# PowerStage.net
KiCad netlist of a schematic drawn in Altium Designer
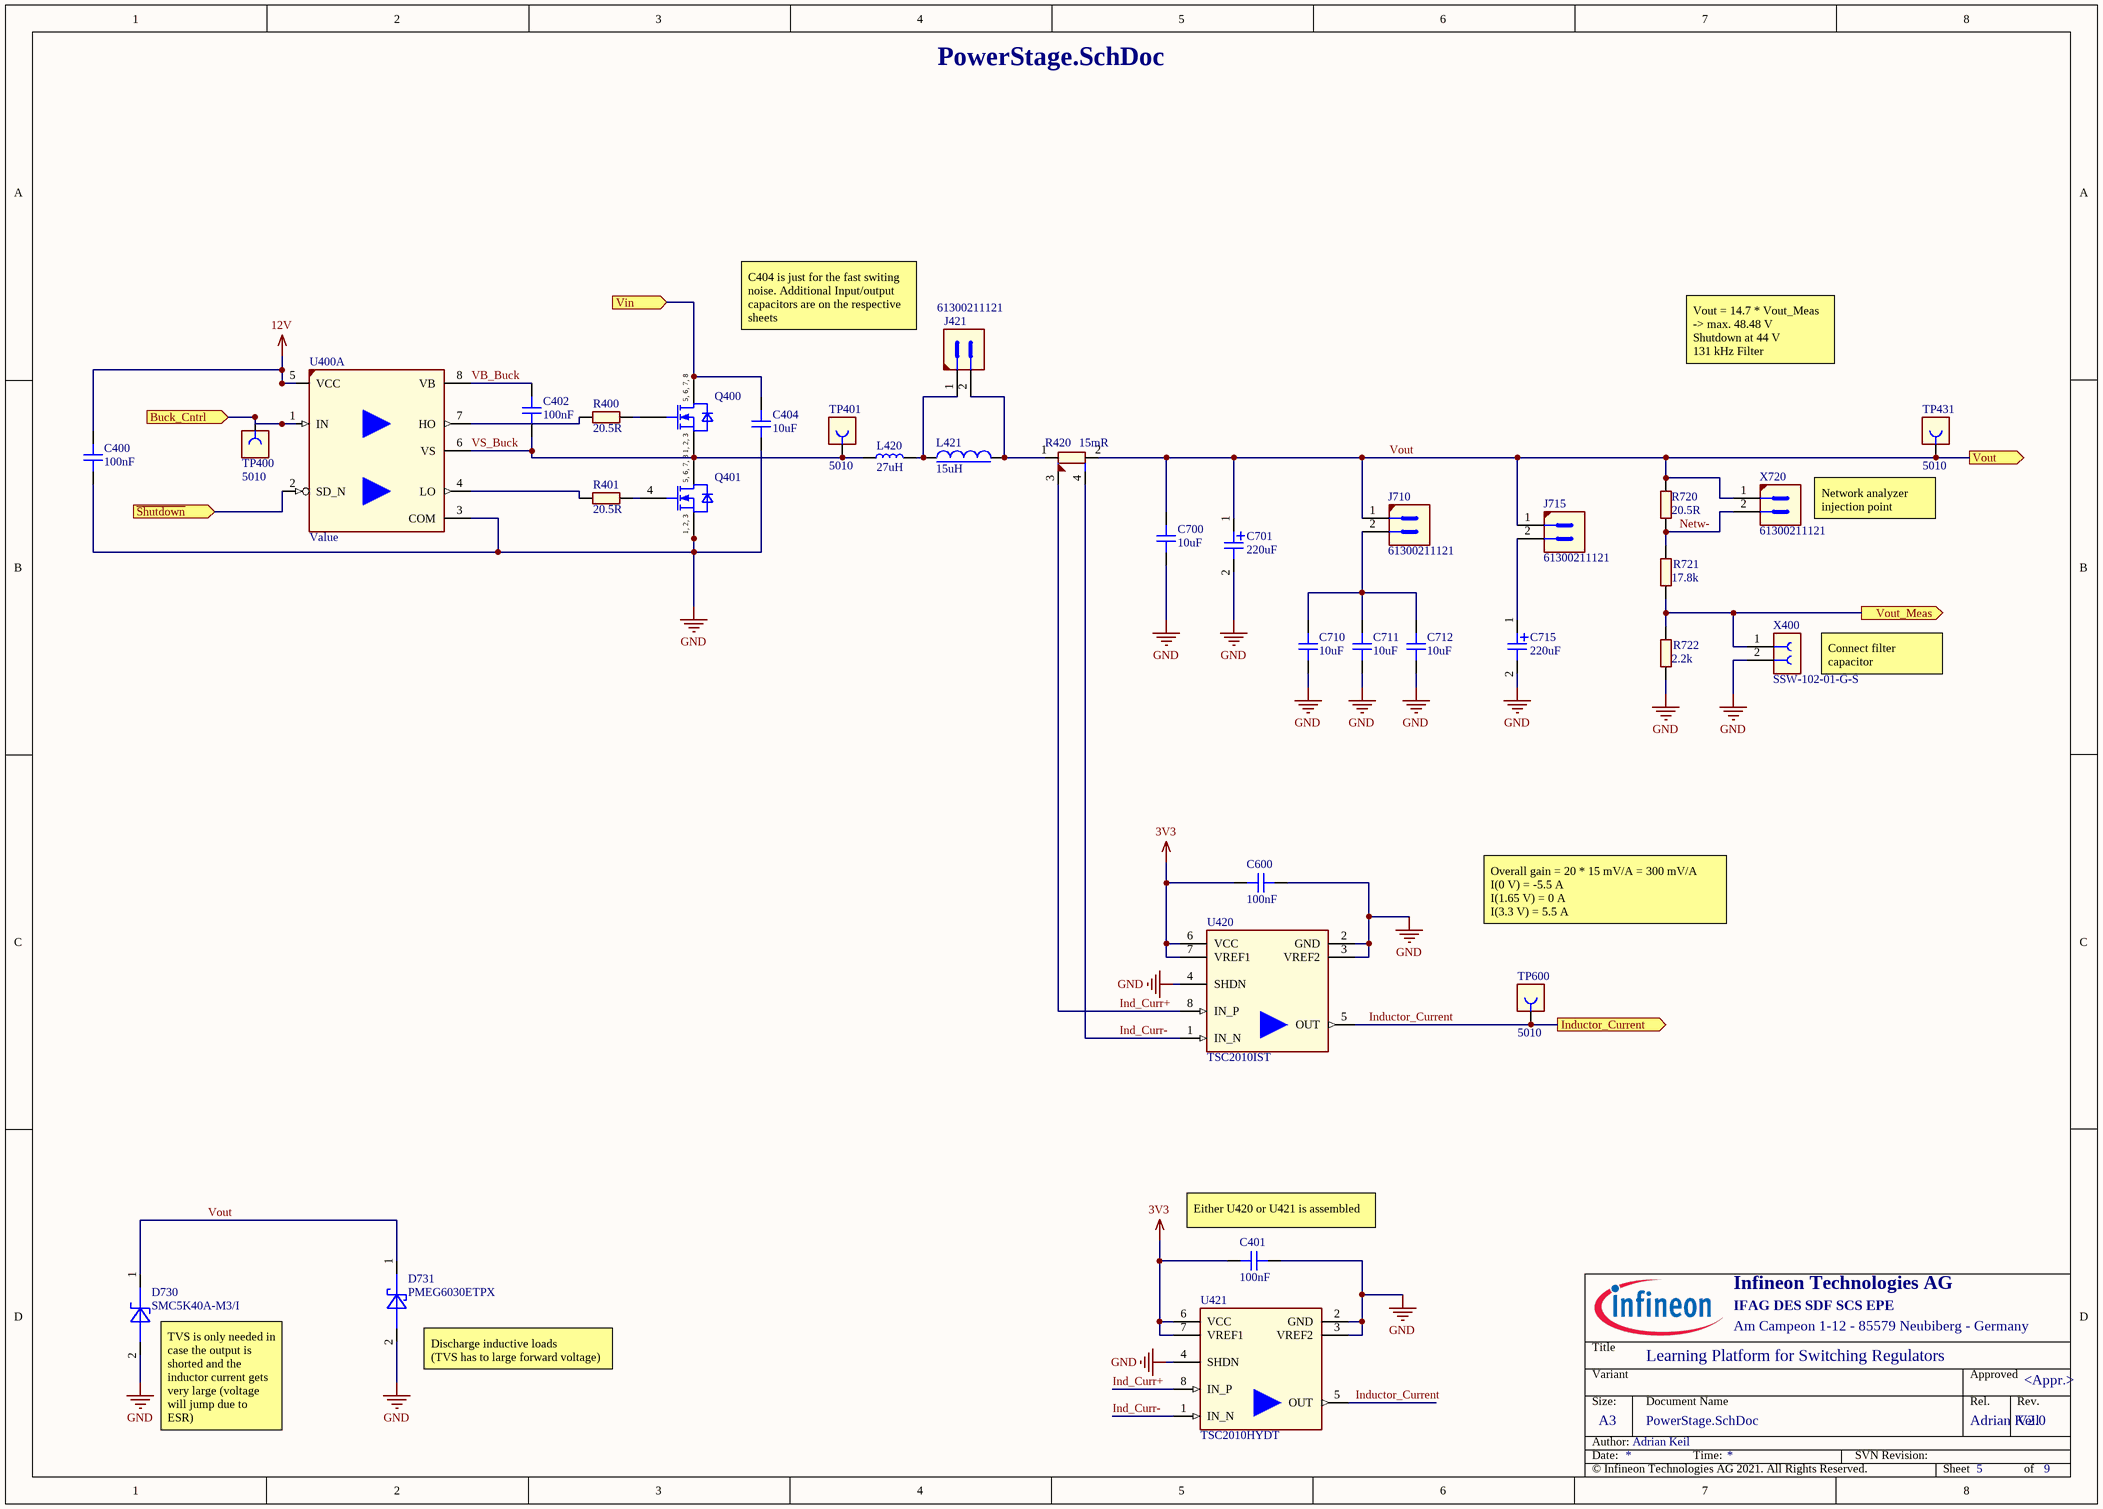
[diagram p0: PowerStage.SchDoc]

(export (version "E")
  (design (tool "Eeschema 10.0.6"))
  (components
    (comp (ref "C400")
      (value "100nF")
      (footprint "CAPC3216X125N-0")
      (description "CAP / CERA / 100nF / 50V / 10% / X7R (EIA) / -55°C to 125°C / 1206(3216) / SMD / -")
      (fields (field (name "LEGACY PARTNUMBER") "CAP01005660") (field (name "MANUFACTURER") "MuRata"))
      (libsource (lib "PCBLibraryData") (part "CAP-SGL-STD-02P_00000001"))
    )
    (comp (ref "C401")
      (value "100nF")
      (footprint "CAPC3216X125N-0")
      (description "CAP / CERA / 100nF / 50V / 10% / X7R (EIA) / -55°C to 125°C / 1206(3216) / SMD / -")
      (fields (field (name "LEGACY PARTNUMBER") "CAP01005660") (field (name "MANUFACTURER") "MuRata"))
      (libsource (lib "PCBLibraryData") (part "CAP-SGL-STD-02P_00000001"))
    )
    (comp (ref "C402")
      (value "100nF")
      (footprint "CAPC3216X125N-0")
      (description "CAP / CERA / 100nF / 50V / 10% / X7R (EIA) / -55°C to 125°C / 1206(3216) / SMD / -")
      (fields (field (name "LEGACY PARTNUMBER") "CAP01005660") (field (name "MANUFACTURER") "MuRata"))
      (libsource (lib "PCBLibraryData") (part "CAP-SGL-STD-02P_00000001"))
    )
    (comp (ref "C404")
      (value "10uF")
      (footprint "CAPC3216X190N-1")
      (description "CAP / CERA / 10uF / 50V / 20% / X5R (EIA) / -55°C to 85°C / 1206 (3216) / SMD / -")
      (fields (field (name "MANUFACTURER") "Taiyo Yuden"))
      (libsource (lib "PCBLibraryData") (part "CAP-SGL-STD-02P_00000001"))
    )
    (comp (ref "C600")
      (value "100nF")
      (footprint "CAPC3216X125N-0")
      (description "CAP / CERA / 100nF / 50V / 10% / X7R (EIA) / -55°C to 125°C / 1206(3216) / SMD / -")
      (fields (field (name "LEGACY PARTNUMBER") "CAP01005660") (field (name "MANUFACTURER") "MuRata"))
      (libsource (lib "PCBLibraryData") (part "CAP-SGL-STD-02P_00000001"))
    )
    (comp (ref "C700")
      (value "10uF")
      (footprint "CAPC3216X190N-1")
      (description "CAP / CERA / 10uF / 50V / 20% / X5R (EIA) / -55°C to 85°C / 1206 (3216) / SMD / -")
      (fields (field (name "MANUFACTURER") "Taiyo Yuden"))
      (libsource (lib "PCBLibraryData") (part "CAP-SGL-STD-02P_00000001"))
    )
    (comp (ref "C701")
      (value "220uF")
      (footprint "CAPAE1030X1050N-3")
      (fields (field (name "MANUFACTURER") "Nippon Chemi-Con"))
      (libsource (lib "PCBLibraryData") (part "CAP-SGL-POL-02P_00000002"))
    )
    (comp (ref "C710")
      (value "10uF")
      (footprint "CAPC3216X190N-1")
      (description "CAP / CERA / 10uF / 50V / 20% / X5R (EIA) / -55°C to 85°C / 1206 (3216) / SMD / -")
      (fields (field (name "MANUFACTURER") "Taiyo Yuden"))
      (libsource (lib "PCBLibraryData") (part "CAP-SGL-STD-02P_00000001"))
    )
    (comp (ref "C711")
      (value "10uF")
      (footprint "CAPC3216X190N-1")
      (description "CAP / CERA / 10uF / 50V / 20% / X5R (EIA) / -55°C to 85°C / 1206 (3216) / SMD / -")
      (fields (field (name "MANUFACTURER") "Taiyo Yuden"))
      (libsource (lib "PCBLibraryData") (part "CAP-SGL-STD-02P_00000001"))
    )
    (comp (ref "C712")
      (value "10uF")
      (footprint "CAPC3216X190N-1")
      (description "CAP / CERA / 10uF / 50V / 20% / X5R (EIA) / -55°C to 85°C / 1206 (3216) / SMD / -")
      (fields (field (name "MANUFACTURER") "Taiyo Yuden"))
      (libsource (lib "PCBLibraryData") (part "CAP-SGL-STD-02P_00000001"))
    )
    (comp (ref "C715")
      (value "220uF")
      (footprint "CAPAE1030X1050N-3")
      (fields (field (name "MANUFACTURER") "Nippon Chemi-Con"))
      (libsource (lib "PCBLibraryData") (part "CAP-SGL-POL-02P_00000002"))
    )
    (comp (ref "D730")
      (value "SMC5K40A-M3/I")
      (footprint "DIOM7959X262N")
      (description "Surface Mount Transient Voltage Suppressors, Unidirectional, Very Fast Response Time")
      (fields (field (name "MANUFACTURER") "Vishay"))
      (libsource (lib "PCBLibraryData") (part "d_tvs_a"))
    )
    (comp (ref "D731")
      (value "PMEG6030ETPX")
      (footprint "SODFL4725X110N")
      (description "DIODE SCHOTTKY 60V 3A SOD128")
      (fields (field (name "MANUFACTURER") "Nexperia"))
      (libsource (lib "PCBLibraryData") (part "d_schottky_a"))
    )
    (comp (ref "J421")
      (value "61300211121")
      (footprint "CON-M-THT-61300211121")
      (description "Header, 2.54mm Pitch, 2 pin, Vertical, Single Row")
      (fields
        (field (name "LEGACY PARTNUMBER") "CON01500943")
        (field (name "MANUFACTURER") "Wurth Elektronik")
      )
      (libsource (lib "") (part "Header 2_1"))
    )
    (comp (ref "J710")
      (value "61300211121")
      (footprint "CON-M-THT-61300211121")
      (description "Header, 2.54mm Pitch, 2 pin, Vertical, Single Row")
      (fields
        (field (name "LEGACY PARTNUMBER") "CON01500943")
        (field (name "MANUFACTURER") "Wurth Elektronik")
      )
      (libsource (lib "PCBLibraryData") (part "Header 2"))
    )
    (comp (ref "J715")
      (value "61300211121")
      (footprint "CON-M-THT-61300211121")
      (description "Header, 2.54mm Pitch, 2 pin, Vertical, Single Row")
      (fields
        (field (name "LEGACY PARTNUMBER") "CON01500943")
        (field (name "MANUFACTURER") "Wurth Elektronik")
      )
      (libsource (lib "PCBLibraryData") (part "Header 2"))
    )
    (comp (ref "L420")
      (value "27uH")
      (footprint "INDM120120X1000N")
      (fields (field (name "MANUFACTURER") "Wurth Elektronik"))
      (libsource (lib "PCBLibraryData") (part "IND-SGL-STD-02P_00000015"))
    )
    (comp (ref "L421")
      (value "15uH")
      (footprint "IND-SMD-SRP6060FA")
      (fields (field (name "MANUFACTURER") "Bourns"))
      (libsource (lib "PCBLibraryData") (part "IND-SGL-STD-COR-02P_00000016"))
    )
    (comp (ref "Q400")
      (value "igfet_n_ch_enh_dio_1s2s3s4g5d6d7d8d_8p")
      (footprint "INF-PG-PQFN-5X6BEG")
      (description "HEXFET Power MOSFET, VDS 60V, RDS(on) max 14.4 mO")
      (fields (field (name "MANUFACTURER") "Infineon Technologies"))
      (libsource (lib "PCBLibraryData") (part "igfet_n_ch_enh_dio_1s2s3s4g5d6d7d8d_8p"))
    )
    (comp (ref "Q401")
      (value "igfet_n_ch_enh_dio_1s2s3s4g5d6d7d8d_8p")
      (footprint "INF-PG-PQFN-5X6BEG")
      (description "HEXFET Power MOSFET, VDS 60V, RDS(on) max 14.4 mO")
      (fields (field (name "MANUFACTURER") "Infineon Technologies"))
      (libsource (lib "") (part "igfet_n_ch_enh_dio_1s2s3s4g5d6d7d8d_8p_1"))
    )
    (comp (ref "R400")
      (value "20.5R")
      (footprint "RESC3216X60N")
      (description "RES / STD / 20.5R / 250mW / 1% / 100ppm/K / -55°C to 155°C / 1206(3216) / SMD / -")
      (fields (field (name "LEGACY PARTNUMBER") "RES01802548") (field (name "MANUFACTURER") "Vishay"))
      (libsource (lib "PCBLibraryData") (part "RES-SGL-STD-02P_00000006"))
    )
    (comp (ref "R401")
      (value "20.5R")
      (footprint "RESC3216X60N")
      (description "RES / STD / 20.5R / 250mW / 1% / 100ppm/K / -55°C to 155°C / 1206(3216) / SMD / -")
      (fields (field (name "LEGACY PARTNUMBER") "RES01802548") (field (name "MANUFACTURER") "Vishay"))
      (libsource (lib "PCBLibraryData") (part "RES-SGL-STD-02P_00000006"))
    )
    (comp (ref "R420")
      (value "15mR")
      (footprint "RES-SMD-L4T12")
      (description "RES / STD / 15mR / 500mW / 1% / 75ppm/K / -55°C to 155°C / 1206 (3216) / SMD / -")
      (fields (field (name "MANUFACTURER") "Ohmite"))
      (libsource (lib "PCBLibraryData") (part "RES-SHT-STD-04P_00097BE5"))
    )
    (comp (ref "R720")
      (value "20.5R")
      (footprint "RESC3216X60N")
      (description "RES / STD / 20.5R / 250mW / 1% / 100ppm/K / -55°C to 155°C / 1206(3216) / SMD / -")
      (fields (field (name "LEGACY PARTNUMBER") "RES01802548") (field (name "MANUFACTURER") "Vishay"))
      (libsource (lib "") (part "RES-SGL-STD-02P_00000006_1"))
    )
    (comp (ref "R721")
      (value "17.8k")
      (footprint "RESC3216X60N")
      (description "RES / STD / 17.8k / 250mW / 1% / 100ppm/K / -55°C to 155°C / 1206(3216) / SMD / -")
      (fields (field (name "LEGACY PARTNUMBER") "RES01802883") (field (name "MANUFACTURER") "Vishay"))
      (libsource (lib "") (part "RES-SGL-STD-02P_00000006_1"))
    )
    (comp (ref "R722")
      (value "2.2k")
      (footprint "RESC3216X60N")
      (description "RES / STD / 2.2k / 250mW / 1% / 100ppm/K / -55°C to 155°C / 1206(3216) / SMD / -")
      (fields (field (name "LEGACY PARTNUMBER") "RES01802779") (field (name "MANUFACTURER") "Vishay"))
      (libsource (lib "") (part "RES-SGL-STD-02P_00000006_2"))
    )
    (comp (ref "TP400")
      (value "5010")
      (footprint "CON-THT-TP-5010")
      (description "PC Test Point-Multipurpose THT, Red")
      (fields
        (field (name "LEGACY PARTNUMBER") "CON01500529")
        (field (name "MANUFACTURER") "Keystone Electronics Corp.")
      )
      (libsource (lib "") (part "connector_1_f_1"))
    )
    (comp (ref "TP401")
      (value "5010")
      (footprint "CON-THT-TP-5010")
      (description "PC Test Point-Multipurpose THT, Red")
      (fields
        (field (name "LEGACY PARTNUMBER") "CON01500529")
        (field (name "MANUFACTURER") "Keystone Electronics Corp.")
      )
      (libsource (lib "PCBLibraryData") (part "connector_1_f"))
    )
    (comp (ref "TP431")
      (value "5010")
      (footprint "CON-THT-TP-5010")
      (description "PC Test Point-Multipurpose THT, Red")
      (fields
        (field (name "LEGACY PARTNUMBER") "CON01500529")
        (field (name "MANUFACTURER") "Keystone Electronics Corp.")
      )
      (libsource (lib "PCBLibraryData") (part "connector_1_f"))
    )
    (comp (ref "TP600")
      (value "5010")
      (footprint "CON-THT-TP-5010")
      (description "PC Test Point-Multipurpose THT, Red")
      (fields
        (field (name "LEGACY PARTNUMBER") "CON01500529")
        (field (name "MANUFACTURER") "Keystone Electronics Corp.")
      )
      (libsource (lib "PCBLibraryData") (part "connector_1_f"))
    )
    (comp (ref "U400")
      (value "Value")
      (footprint "SOIC127P600X172-8N-1-V")
      (description "Driving IGBTs, enhancement mode N-Channel MOSFETs in various power electronic applications")
      (fields (field (name "MANUFACTURER") "Infineon Technologies"))
      (libsource (lib "PCBLibraryData") (part "2ED2184S06F"))
    )
    (comp (ref "U420")
      (value "TSC2010IST")
      (footprint "SOIC127P600X175-8N-16")
      (description "Precision bidirectional current sense amplifier")
      (fields (field (name "MANUFACTURER") "STMicroelectronics"))
      (libsource (lib "PCBLibraryData") (part "TSC201XHYDT"))
    )
    (comp (ref "U421")
      (value "TSC2010HYDT")
      (footprint "SOIC127P600X175-8N-16")
      (description "Precision bidirectional current sense amplifier")
      (fields (field (name "MANUFACTURER") "STMicroelectronics"))
      (libsource (lib "PCBLibraryData") (part "TSC201XHYDT"))
    )
    (comp (ref "X400")
      (value "SSW-102-01-G-S")
      (footprint "CON-F-THT-SSW-102-01-G-S")
      (description "Through Hole .025'' SQ Post Socket, 2.54mm pitch, 2 Pins")
      (fields (field (name "MANUFACTURER") "Samtec"))
      (libsource (lib "PCBLibraryData") (part "Socket 2"))
    )
    (comp (ref "X720")
      (value "61300211121")
      (footprint "CON-M-THT-61300211121")
      (description "Header, 2.54mm Pitch, 2 pin, Vertical, Single Row")
      (fields
        (field (name "LEGACY PARTNUMBER") "CON01500943")
        (field (name "MANUFACTURER") "Wurth Elektronik")
      )
      (libsource (lib "PCBLibraryData") (part "Header 2"))
    )
  )
  (nets
    (net (code "1") (name "/Buck_Cntrl") (class "Default")
      (node (ref "TP400") (pin "1") (pinfunction "1_1") (pintype "passive"))
      (node (ref "U400") (pin "1") (pinfunction "IN_1") (pintype "input"))
    )
    (net (code "2") (name "/Ind_Curr+") (class "Default")
      (node (ref "R420") (pin "3") (pinfunction "I1_3") (pintype "passive"))
      (node (ref "U420") (pin "8") (pinfunction "IN_P_8") (pintype "input"))
      (node (ref "U421") (pin "8") (pinfunction "IN_P_8") (pintype "input"))
    )
    (net (code "3") (name "/Ind_Curr-") (class "Default")
      (node (ref "R420") (pin "4") (pinfunction "I2_4") (pintype "passive"))
      (node (ref "U420") (pin "1") (pinfunction "IN_N_1") (pintype "input"))
      (node (ref "U421") (pin "1") (pinfunction "IN_N_1") (pintype "input"))
    )
    (net (code "4") (name "/Inductor_Current") (class "Default")
      (node (ref "TP600") (pin "1") (pinfunction "1_1") (pintype "passive"))
      (node (ref "U420") (pin "5") (pinfunction "OUT_5") (pintype "output"))
      (node (ref "U421") (pin "5") (pinfunction "OUT_5") (pintype "output"))
    )
    (net (code "5") (name "/Netw-") (class "Default")
      (node (ref "R720") (pin "1") (pinfunction "1_1") (pintype "passive"))
      (node (ref "R721") (pin "2") (pinfunction "2_2") (pintype "passive"))
      (node (ref "X720") (pin "2") (pinfunction "2_2") (pintype "passive"))
    )
    (net (code "6") (name "/Shutdown") (class "Default")
      (node (ref "U400") (pin "2") (pinfunction "SD_N_2") (pintype "input"))
    )
    (net (code "7") (name "/VB_Buck") (class "Default")
      (node (ref "C402") (pin "2") (pinfunction "2_2") (pintype "passive"))
      (node (ref "U400") (pin "8") (pinfunction "VB_8") (pintype "power_in"))
    )
    (net (code "8") (name "/VS_Buck") (class "Default")
      (node (ref "C402") (pin "1") (pinfunction "1_1") (pintype "passive"))
      (node (ref "L420") (pin "1") (pinfunction "1_1") (pintype "passive"))
      (node (ref "Q400") (pin "1") (pinfunction "SOURCE_1") (pintype "passive"))
      (node (ref "Q400") (pin "2") (pinfunction "SOURCE_2") (pintype "passive"))
      (node (ref "Q400") (pin "3") (pinfunction "SOURCE_3") (pintype "passive"))
      (node (ref "Q401") (pin "5") (pinfunction "DRAIN_5") (pintype "passive"))
      (node (ref "Q401") (pin "6") (pinfunction "DRAIN_6") (pintype "passive"))
      (node (ref "Q401") (pin "7") (pinfunction "DRAIN_7") (pintype "passive"))
      (node (ref "Q401") (pin "8") (pinfunction "DRAIN_8") (pintype "passive"))
      (node (ref "TP401") (pin "1") (pinfunction "1_1") (pintype "passive"))
      (node (ref "U400") (pin "6") (pinfunction "VS_6") (pintype "power_in"))
    )
    (net (code "9") (name "/Vin") (class "Default")
      (node (ref "C404") (pin "2") (pinfunction "2_2") (pintype "passive"))
      (node (ref "Q400") (pin "5") (pinfunction "DRAIN_5") (pintype "passive"))
      (node (ref "Q400") (pin "6") (pinfunction "DRAIN_6") (pintype "passive"))
      (node (ref "Q400") (pin "7") (pinfunction "DRAIN_7") (pintype "passive"))
      (node (ref "Q400") (pin "8") (pinfunction "DRAIN_8") (pintype "passive"))
    )
    (net (code "10") (name "/Vout") (class "Default")
      (node (ref "C700") (pin "2") (pinfunction "2_2") (pintype "passive"))
      (node (ref "C701") (pin "1") (pinfunction "1_1") (pintype "passive"))
      (node (ref "D730") (pin "1") (pinfunction "CATHODE_1") (pintype "passive"))
      (node (ref "D731") (pin "1") (pinfunction "Cathode_1") (pintype "passive"))
      (node (ref "J710") (pin "1") (pinfunction "1_1") (pintype "passive"))
      (node (ref "J715") (pin "1") (pinfunction "1_1") (pintype "passive"))
      (node (ref "R420") (pin "2") (pinfunction "V2_2") (pintype "passive"))
      (node (ref "R720") (pin "2") (pinfunction "2_2") (pintype "passive"))
      (node (ref "TP431") (pin "1") (pinfunction "1_1") (pintype "passive"))
      (node (ref "X720") (pin "1") (pinfunction "1_1") (pintype "passive"))
    )
    (net (code "11") (name "/Vout_Meas") (class "Default")
      (node (ref "R721") (pin "1") (pinfunction "1_1") (pintype "passive"))
      (node (ref "R722") (pin "1") (pinfunction "1_1") (pintype "passive"))
      (node (ref "X400") (pin "1") (pinfunction "1_1") (pintype "passive"))
    )
    (net (code "12") (name "3V3") (class "Default")
      (node (ref "C401") (pin "2") (pinfunction "2_2") (pintype "passive"))
      (node (ref "C600") (pin "2") (pinfunction "2_2") (pintype "passive"))
      (node (ref "U420") (pin "6") (pinfunction "VCC_6") (pintype "power_in"))
      (node (ref "U420") (pin "7") (pinfunction "VREF1_7") (pintype "power_in"))
      (node (ref "U421") (pin "6") (pinfunction "VCC_6") (pintype "power_in"))
      (node (ref "U421") (pin "7") (pinfunction "VREF1_7") (pintype "power_in"))
    )
    (net (code "13") (name "12V") (class "Default")
      (node (ref "C400") (pin "2") (pinfunction "2_2") (pintype "passive"))
      (node (ref "U400") (pin "5") (pinfunction "VCC_5") (pintype "power_in"))
    )
    (net (code "14") (name "GND") (class "Default")
      (node (ref "C400") (pin "1") (pinfunction "1_1") (pintype "passive"))
      (node (ref "C401") (pin "1") (pinfunction "1_1") (pintype "passive"))
      (node (ref "C404") (pin "1") (pinfunction "1_1") (pintype "passive"))
      (node (ref "C600") (pin "1") (pinfunction "1_1") (pintype "passive"))
      (node (ref "C700") (pin "1") (pinfunction "1_1") (pintype "passive"))
      (node (ref "C701") (pin "2") (pinfunction "2_2") (pintype "passive"))
      (node (ref "C710") (pin "1") (pinfunction "1_1") (pintype "passive"))
      (node (ref "C711") (pin "1") (pinfunction "1_1") (pintype "passive"))
      (node (ref "C712") (pin "1") (pinfunction "1_1") (pintype "passive"))
      (node (ref "C715") (pin "2") (pinfunction "2_2") (pintype "passive"))
      (node (ref "D730") (pin "2") (pinfunction "ANODE_2") (pintype "passive"))
      (node (ref "D731") (pin "2") (pinfunction "Anode_2") (pintype "passive"))
      (node (ref "Q401") (pin "1") (pinfunction "SOURCE_1") (pintype "passive"))
      (node (ref "Q401") (pin "2") (pinfunction "SOURCE_2") (pintype "passive"))
      (node (ref "Q401") (pin "3") (pinfunction "SOURCE_3") (pintype "passive"))
      (node (ref "R722") (pin "2") (pinfunction "2_2") (pintype "passive"))
      (node (ref "U400") (pin "3") (pinfunction "COM_3") (pintype "passive"))
      (node (ref "U420") (pin "2") (pinfunction "GND_2") (pintype "power_in"))
      (node (ref "U420") (pin "3") (pinfunction "VREF2_3") (pintype "power_in"))
      (node (ref "U420") (pin "4") (pinfunction "SHDN_4") (pintype "passive"))
      (node (ref "U421") (pin "2") (pinfunction "GND_2") (pintype "power_in"))
      (node (ref "U421") (pin "3") (pinfunction "VREF2_3") (pintype "power_in"))
      (node (ref "U421") (pin "4") (pinfunction "SHDN_4") (pintype "passive"))
      (node (ref "X400") (pin "2") (pinfunction "2_2") (pintype "passive"))
    )
    (net (code "15") (name "Net-(C710-Pad2)") (class "Default")
      (node (ref "C710") (pin "2") (pinfunction "2_2") (pintype "passive"))
      (node (ref "C711") (pin "2") (pinfunction "2_2") (pintype "passive"))
      (node (ref "C712") (pin "2") (pinfunction "2_2") (pintype "passive"))
      (node (ref "J710") (pin "2") (pinfunction "2_2") (pintype "passive"))
    )
    (net (code "16") (name "Net-(C715-Pad1)") (class "Default")
      (node (ref "C715") (pin "1") (pinfunction "1_1") (pintype "passive"))
      (node (ref "J715") (pin "2") (pinfunction "2_2") (pintype "passive"))
    )
    (net (code "17") (name "Net-(J421-Pad1)") (class "Default")
      (node (ref "J421") (pin "1") (pinfunction "1_1") (pintype "passive"))
      (node (ref "L420") (pin "2") (pinfunction "2_2") (pintype "passive"))
      (node (ref "L421") (pin "1") (pinfunction "1_1") (pintype "passive"))
    )
    (net (code "18") (name "Net-(Q400-GATE)") (class "Default")
      (node (ref "Q400") (pin "4") (pinfunction "GATE_4") (pintype "passive"))
      (node (ref "R400") (pin "1") (pinfunction "1_1") (pintype "passive"))
    )
    (net (code "19") (name "Net-(Q401-GATE)") (class "Default")
      (node (ref "Q401") (pin "4") (pinfunction "GATE_4") (pintype "passive"))
      (node (ref "R401") (pin "1") (pinfunction "1_1") (pintype "passive"))
    )
    (net (code "20") (name "Net-(R420-V1)") (class "Default")
      (node (ref "J421") (pin "2") (pinfunction "2_2") (pintype "passive"))
      (node (ref "L421") (pin "2") (pinfunction "2_2") (pintype "passive"))
      (node (ref "R420") (pin "1") (pinfunction "V1_1") (pintype "passive"))
    )
    (net (code "21") (name "Net-(U400-HO)") (class "Default")
      (node (ref "R400") (pin "2") (pinfunction "2_2") (pintype "passive"))
      (node (ref "U400") (pin "7") (pinfunction "HO_7") (pintype "output"))
    )
    (net (code "22") (name "Net-(U400-LO)") (class "Default")
      (node (ref "R401") (pin "2") (pinfunction "2_2") (pintype "passive"))
      (node (ref "U400") (pin "4") (pinfunction "LO_4") (pintype "output"))
    )
  )
)
